# X07-X00.net
KiCad netlist of a schematic drawn in Altium Designer
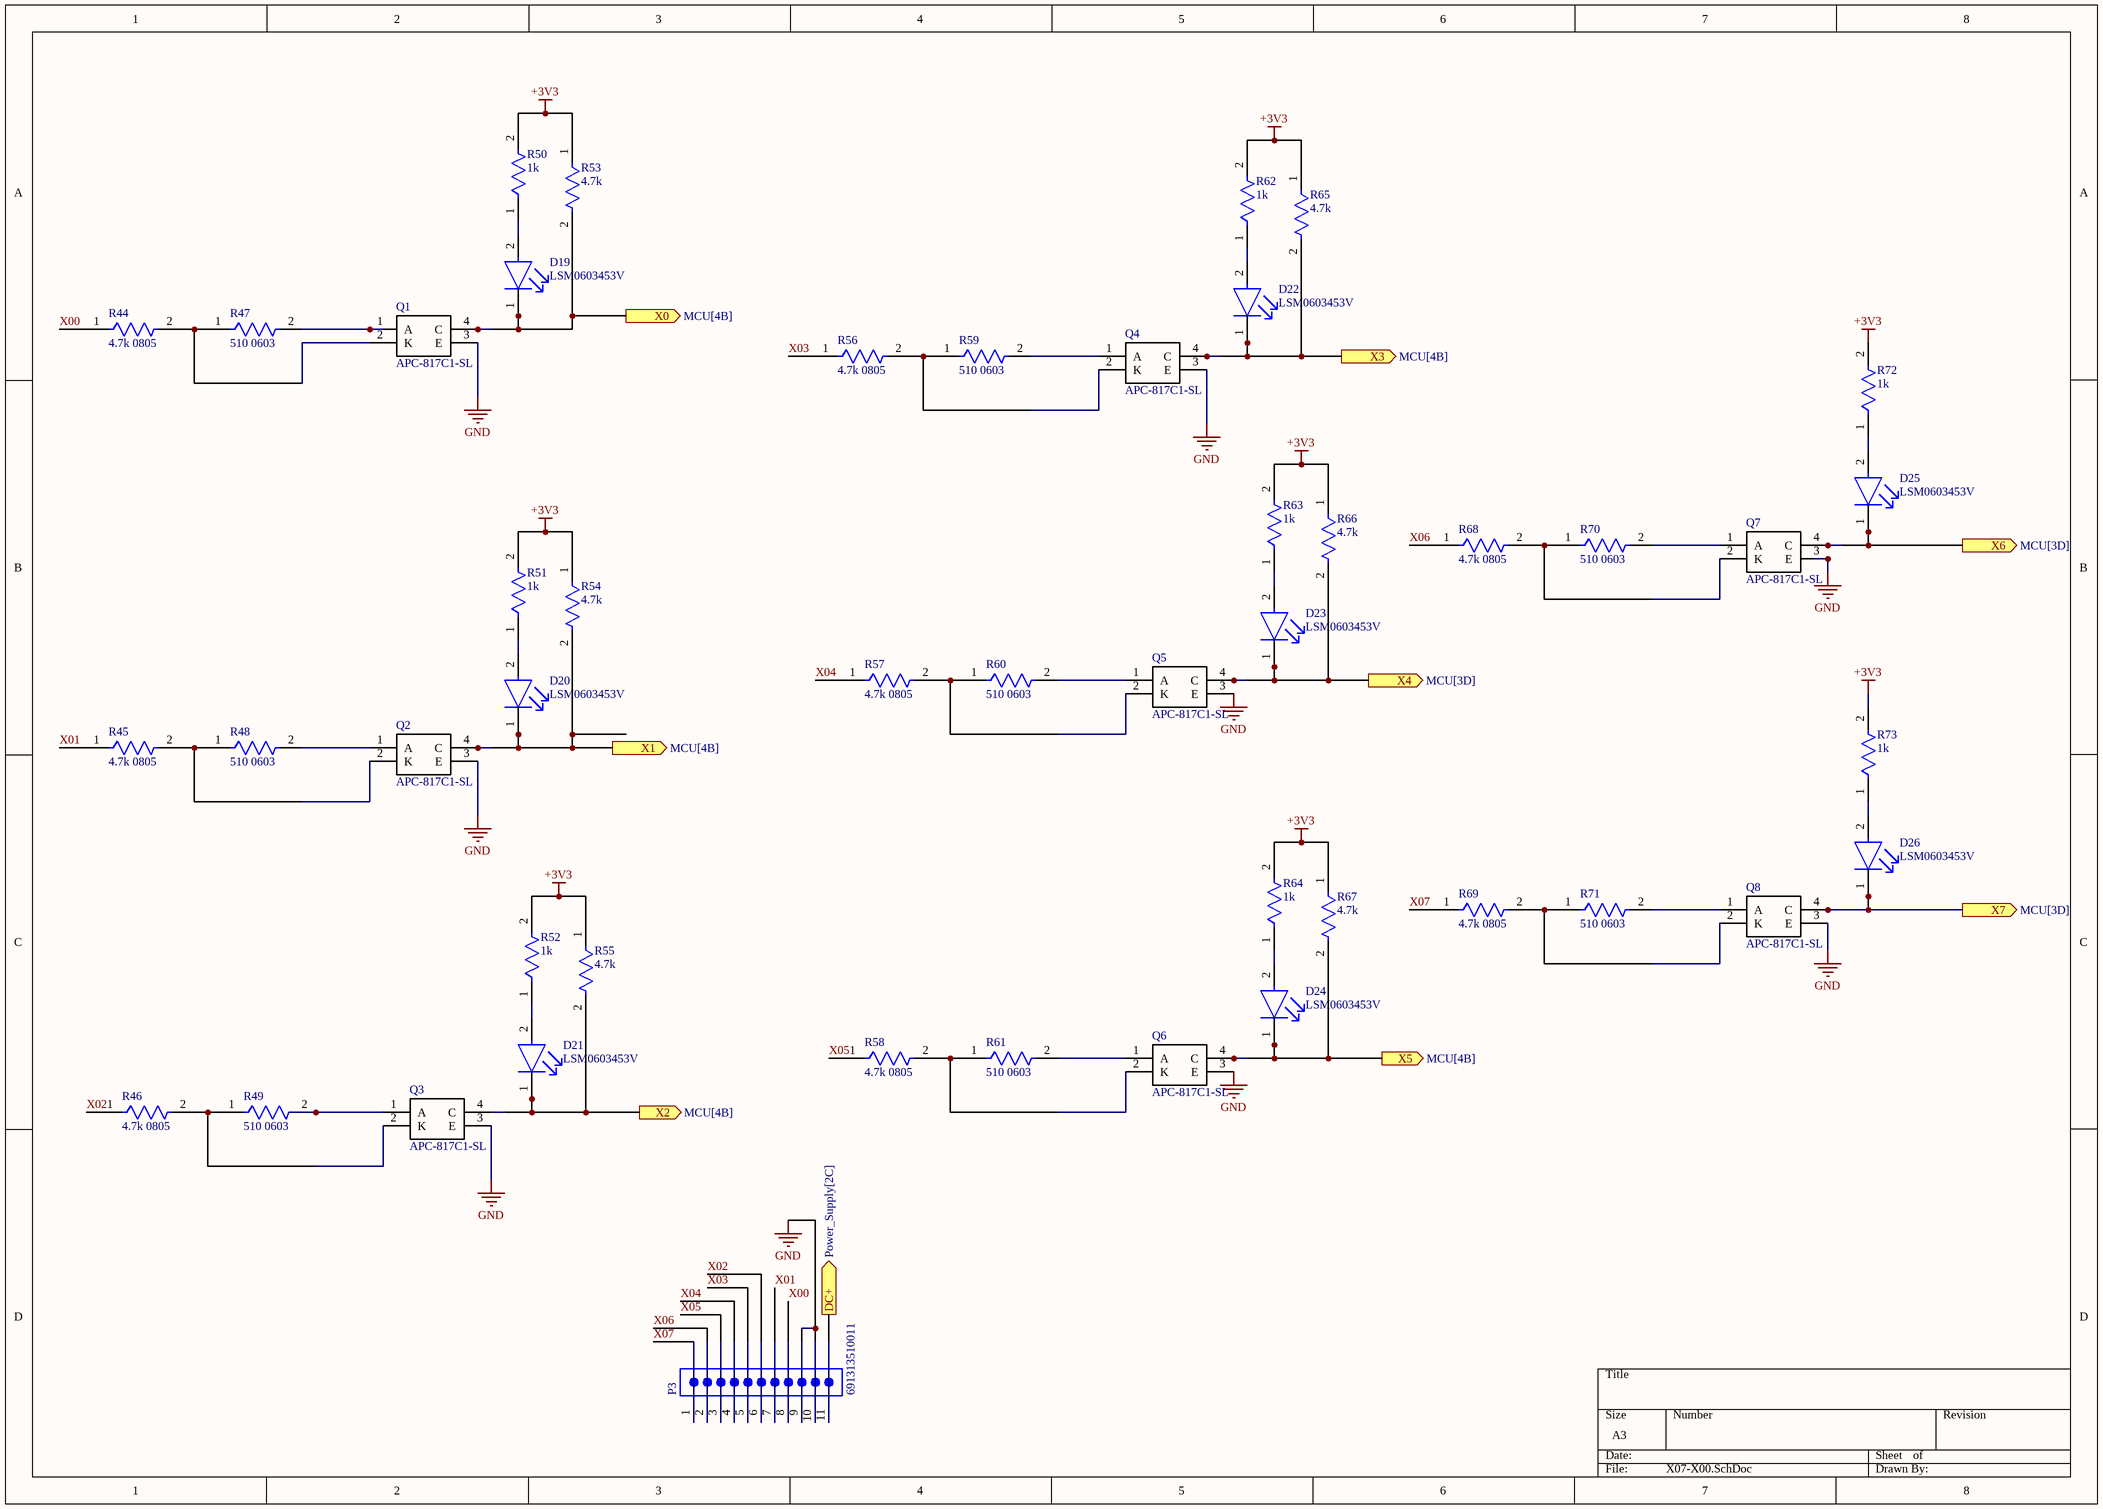
[diagram p0: X07-X00.SchDoc]

(export (version "E")
  (design (tool "Eeschema 10.0.6"))
  (components
    (comp (ref "D19")
      (value "LSM0603453V")
      (footprint "FP-LSM0603453V-MFG")
      (description "LSM0603453V LED SM 0603 3V -/1000/-mcd Green")
      (libsource (lib "Altium Content Vault") (part "8706943c75ba83719d021d2fdc84c58"))
    )
    (comp (ref "D20")
      (value "LSM0603453V")
      (footprint "FP-LSM0603453V-MFG")
      (description "LSM0603453V LED SM 0603 3V -/1000/-mcd Green")
      (libsource (lib "Altium Content Vault") (part "8706943c75ba83719d021d2fdc84c58"))
    )
    (comp (ref "D21")
      (value "LSM0603453V")
      (footprint "FP-LSM0603453V-MFG")
      (description "LSM0603453V LED SM 0603 3V -/1000/-mcd Green")
      (libsource (lib "Altium Content Vault") (part "8706943c75ba83719d021d2fdc84c58"))
    )
    (comp (ref "D22")
      (value "LSM0603453V")
      (footprint "FP-LSM0603453V-MFG")
      (description "LSM0603453V LED SM 0603 3V -/1000/-mcd Green")
      (libsource (lib "Altium Content Vault") (part "8706943c75ba83719d021d2fdc84c58"))
    )
    (comp (ref "D23")
      (value "LSM0603453V")
      (footprint "FP-LSM0603453V-MFG")
      (description "LSM0603453V LED SM 0603 3V -/1000/-mcd Green")
      (libsource (lib "Altium Content Vault") (part "8706943c75ba83719d021d2fdc84c58"))
    )
    (comp (ref "D24")
      (value "LSM0603453V")
      (footprint "FP-LSM0603453V-MFG")
      (description "LSM0603453V LED SM 0603 3V -/1000/-mcd Green")
      (libsource (lib "Altium Content Vault") (part "8706943c75ba83719d021d2fdc84c58"))
    )
    (comp (ref "D25")
      (value "LSM0603453V")
      (footprint "FP-LSM0603453V-MFG")
      (description "LSM0603453V LED SM 0603 3V -/1000/-mcd Green")
      (libsource (lib "Altium Content Vault") (part "8706943c75ba83719d021d2fdc84c58"))
    )
    (comp (ref "D26")
      (value "LSM0603453V")
      (footprint "FP-LSM0603453V-MFG")
      (description "LSM0603453V LED SM 0603 3V -/1000/-mcd Green")
      (libsource (lib "Altium Content Vault") (part "8706943c75ba83719d021d2fdc84c58"))
    )
    (comp (ref "P3")
      (value "691313510011")
      (footprint "691313510011")
      (description "Terminal Block, 5.08MM Pitch, Close Horizontal Pcb Header, 300VAC, 11 Pins")
      (libsource (lib "Altium Content Vault") (part "TBL - 1R - 11P - Male"))
    )
    (comp (ref "Q1")
      (value "APC-817C1-SL")
      (footprint "PcbLib1:APC817C1SL")
      (description "Phototransistor")
      (libsource (lib "Schlib1") (part "APC-817C1-SL"))
    )
    (comp (ref "Q2")
      (value "APC-817C1-SL")
      (footprint "PcbLib1:APC817C1SL")
      (description "Phototransistor")
      (libsource (lib "Schlib1") (part "APC-817C1-SL"))
    )
    (comp (ref "Q3")
      (value "APC-817C1-SL")
      (footprint "PcbLib1:APC817C1SL")
      (description "Phototransistor")
      (libsource (lib "Schlib1") (part "APC-817C1-SL"))
    )
    (comp (ref "Q4")
      (value "APC-817C1-SL")
      (footprint "PcbLib1:APC817C1SL")
      (description "Phototransistor")
      (libsource (lib "Schlib1") (part "APC-817C1-SL"))
    )
    (comp (ref "Q5")
      (value "APC-817C1-SL")
      (footprint "PcbLib1:APC817C1SL")
      (description "Phototransistor")
      (libsource (lib "Schlib1") (part "APC-817C1-SL"))
    )
    (comp (ref "Q6")
      (value "APC-817C1-SL")
      (footprint "PcbLib1:APC817C1SL")
      (description "Phototransistor")
      (libsource (lib "Schlib1") (part "APC-817C1-SL"))
    )
    (comp (ref "Q7")
      (value "APC-817C1-SL")
      (footprint "PcbLib1:APC817C1SL")
      (description "Phototransistor")
      (libsource (lib "Schlib1") (part "APC-817C1-SL"))
    )
    (comp (ref "Q8")
      (value "APC-817C1-SL")
      (footprint "PcbLib1:APC817C1SL")
      (description "Phototransistor")
      (libsource (lib "Schlib1") (part "APC-817C1-SL"))
    )
    (comp (ref "R44")
      (value "4.7k 0805")
      (footprint "FP-MCU0805-MFG")
      (description "RES 1.05K OHM 0.5% 1/5W 0805")
      (fields (field (name "TOLERANCE") "0.1%"))
      (libsource (lib "Altium Content Vault") (part "1029c3af85768c4190bb7ad29bc67b5"))
    )
    (comp (ref "R45")
      (value "4.7k 0805")
      (footprint "FP-MCU0805-MFG")
      (description "RES 1.05K OHM 0.5% 1/5W 0805")
      (fields (field (name "TOLERANCE") "0.1%"))
      (libsource (lib "Altium Content Vault") (part "1029c3af85768c4190bb7ad29bc67b5"))
    )
    (comp (ref "R46")
      (value "4.7k 0805")
      (footprint "FP-MCU0805-MFG")
      (description "RES 1.05K OHM 0.5% 1/5W 0805")
      (fields (field (name "TOLERANCE") "0.1%"))
      (libsource (lib "Altium Content Vault") (part "1029c3af85768c4190bb7ad29bc67b5"))
    )
    (comp (ref "R47")
      (value "510 0603")
      (footprint "FP-RMCF0603-IPC_C")
      (description "510Ω ±5% 0.1W 0603 Thick Film Chip Resistor AEC-Q200 compliant")
      (fields (field (name "TOLERANCE") "5%"))
      (libsource (lib "Altium Content Vault") (part "1029c3af85768c4190bb7ad29bc67b5"))
    )
    (comp (ref "R48")
      (value "510 0603")
      (footprint "FP-RMCF0603-IPC_C")
      (description "510Ω ±5% 0.1W 0603 Thick Film Chip Resistor AEC-Q200 compliant")
      (fields (field (name "TOLERANCE") "5%"))
      (libsource (lib "Altium Content Vault") (part "1029c3af85768c4190bb7ad29bc67b5"))
    )
    (comp (ref "R49")
      (value "510 0603")
      (footprint "FP-RMCF0603-IPC_C")
      (description "510Ω ±5% 0.1W 0603 Thick Film Chip Resistor AEC-Q200 compliant")
      (fields (field (name "TOLERANCE") "5%"))
      (libsource (lib "Altium Content Vault") (part "1029c3af85768c4190bb7ad29bc67b5"))
    )
    (comp (ref "R50")
      (value "1k")
      (footprint "FP-MCS0402-IPC_A")
      (description "RES SMD 1.2K OHM 1% 1/10W 0402")
      (libsource (lib "Altium Content Vault") (part "1029c3af85768c4190bb7ad29bc67b5"))
    )
    (comp (ref "R51")
      (value "1k")
      (footprint "FP-MCS0402-IPC_A")
      (description "RES SMD 1.2K OHM 1% 1/10W 0402")
      (libsource (lib "Altium Content Vault") (part "1029c3af85768c4190bb7ad29bc67b5"))
    )
    (comp (ref "R52")
      (value "1k")
      (footprint "FP-MCS0402-IPC_A")
      (description "RES SMD 1.2K OHM 1% 1/10W 0402")
      (libsource (lib "Altium Content Vault") (part "1029c3af85768c4190bb7ad29bc67b5"))
    )
    (comp (ref "R53")
      (value "4.7k")
      (footprint "FP-TFCR0402-IPC_A")
      (description "RES Thin Film,  4.7kΩ, 0.5%, 0.063W, 25ppm/°C, 0402")
      (libsource (lib "Altium Content Vault") (part "1029c3af85768c4190bb7ad29bc67b5"))
    )
    (comp (ref "R54")
      (value "4.7k")
      (footprint "FP-TFCR0402-IPC_A")
      (description "RES Thin Film,  4.7kΩ, 0.5%, 0.063W, 25ppm/°C, 0402")
      (libsource (lib "Altium Content Vault") (part "1029c3af85768c4190bb7ad29bc67b5"))
    )
    (comp (ref "R55")
      (value "4.7k")
      (footprint "FP-TFCR0402-IPC_A")
      (description "RES Thin Film,  4.7kΩ, 0.5%, 0.063W, 25ppm/°C, 0402")
      (libsource (lib "Altium Content Vault") (part "1029c3af85768c4190bb7ad29bc67b5"))
    )
    (comp (ref "R56")
      (value "4.7k 0805")
      (footprint "FP-MCU0805-MFG")
      (description "RES 1.05K OHM 0.5% 1/5W 0805")
      (fields (field (name "TOLERANCE") "0.1%"))
      (libsource (lib "Altium Content Vault") (part "1029c3af85768c4190bb7ad29bc67b5"))
    )
    (comp (ref "R57")
      (value "4.7k 0805")
      (footprint "FP-MCU0805-MFG")
      (description "RES 1.05K OHM 0.5% 1/5W 0805")
      (fields (field (name "TOLERANCE") "0.1%"))
      (libsource (lib "Altium Content Vault") (part "1029c3af85768c4190bb7ad29bc67b5"))
    )
    (comp (ref "R58")
      (value "4.7k 0805")
      (footprint "FP-MCU0805-MFG")
      (description "RES 1.05K OHM 0.5% 1/5W 0805")
      (fields (field (name "TOLERANCE") "0.1%"))
      (libsource (lib "Altium Content Vault") (part "1029c3af85768c4190bb7ad29bc67b5"))
    )
    (comp (ref "R59")
      (value "510 0603")
      (footprint "FP-RMCF0603-IPC_C")
      (description "510Ω ±5% 0.1W 0603 Thick Film Chip Resistor AEC-Q200 compliant")
      (fields (field (name "TOLERANCE") "5%"))
      (libsource (lib "Altium Content Vault") (part "1029c3af85768c4190bb7ad29bc67b5"))
    )
    (comp (ref "R60")
      (value "510 0603")
      (footprint "FP-RMCF0603-IPC_C")
      (description "510Ω ±5% 0.1W 0603 Thick Film Chip Resistor AEC-Q200 compliant")
      (fields (field (name "TOLERANCE") "5%"))
      (libsource (lib "Altium Content Vault") (part "1029c3af85768c4190bb7ad29bc67b5"))
    )
    (comp (ref "R61")
      (value "510 0603")
      (footprint "FP-RMCF0603-IPC_C")
      (description "510Ω ±5% 0.1W 0603 Thick Film Chip Resistor AEC-Q200 compliant")
      (fields (field (name "TOLERANCE") "5%"))
      (libsource (lib "Altium Content Vault") (part "1029c3af85768c4190bb7ad29bc67b5"))
    )
    (comp (ref "R62")
      (value "1k")
      (footprint "FP-MCS0402-IPC_A")
      (description "RES SMD 1.2K OHM 1% 1/10W 0402")
      (libsource (lib "Altium Content Vault") (part "1029c3af85768c4190bb7ad29bc67b5"))
    )
    (comp (ref "R63")
      (value "1k")
      (footprint "FP-MCS0402-IPC_A")
      (description "RES SMD 1.2K OHM 1% 1/10W 0402")
      (libsource (lib "Altium Content Vault") (part "1029c3af85768c4190bb7ad29bc67b5"))
    )
    (comp (ref "R64")
      (value "1k")
      (footprint "FP-MCS0402-IPC_A")
      (description "RES SMD 1.2K OHM 1% 1/10W 0402")
      (libsource (lib "Altium Content Vault") (part "1029c3af85768c4190bb7ad29bc67b5"))
    )
    (comp (ref "R65")
      (value "4.7k")
      (footprint "FP-TFCR0402-IPC_A")
      (description "RES Thin Film,  4.7kΩ, 0.5%, 0.063W, 25ppm/°C, 0402")
      (libsource (lib "Altium Content Vault") (part "1029c3af85768c4190bb7ad29bc67b5"))
    )
    (comp (ref "R66")
      (value "4.7k")
      (footprint "FP-TFCR0402-IPC_A")
      (description "RES Thin Film,  4.7kΩ, 0.5%, 0.063W, 25ppm/°C, 0402")
      (libsource (lib "Altium Content Vault") (part "1029c3af85768c4190bb7ad29bc67b5"))
    )
    (comp (ref "R67")
      (value "4.7k")
      (footprint "FP-TFCR0402-IPC_A")
      (description "RES Thin Film,  4.7kΩ, 0.5%, 0.063W, 25ppm/°C, 0402")
      (libsource (lib "Altium Content Vault") (part "1029c3af85768c4190bb7ad29bc67b5"))
    )
    (comp (ref "R68")
      (value "4.7k 0805")
      (footprint "FP-MCU0805-MFG")
      (description "RES 1.05K OHM 0.5% 1/5W 0805")
      (fields (field (name "TOLERANCE") "0.1%"))
      (libsource (lib "Altium Content Vault") (part "1029c3af85768c4190bb7ad29bc67b5"))
    )
    (comp (ref "R69")
      (value "4.7k 0805")
      (footprint "FP-MCU0805-MFG")
      (description "RES 1.05K OHM 0.5% 1/5W 0805")
      (fields (field (name "TOLERANCE") "0.1%"))
      (libsource (lib "Altium Content Vault") (part "1029c3af85768c4190bb7ad29bc67b5"))
    )
    (comp (ref "R70")
      (value "510 0603")
      (footprint "FP-RMCF0603-IPC_C")
      (description "510Ω ±5% 0.1W 0603 Thick Film Chip Resistor AEC-Q200 compliant")
      (fields (field (name "TOLERANCE") "5%"))
      (libsource (lib "Altium Content Vault") (part "1029c3af85768c4190bb7ad29bc67b5"))
    )
    (comp (ref "R71")
      (value "510 0603")
      (footprint "FP-RMCF0603-IPC_C")
      (description "510Ω ±5% 0.1W 0603 Thick Film Chip Resistor AEC-Q200 compliant")
      (fields (field (name "TOLERANCE") "5%"))
      (libsource (lib "Altium Content Vault") (part "1029c3af85768c4190bb7ad29bc67b5"))
    )
    (comp (ref "R72")
      (value "1k")
      (footprint "FP-MCS0402-IPC_A")
      (description "RES SMD 1.2K OHM 1% 1/10W 0402")
      (libsource (lib "Altium Content Vault") (part "1029c3af85768c4190bb7ad29bc67b5"))
    )
    (comp (ref "R73")
      (value "1k")
      (footprint "FP-MCS0402-IPC_A")
      (description "RES SMD 1.2K OHM 1% 1/10W 0402")
      (libsource (lib "Altium Content Vault") (part "1029c3af85768c4190bb7ad29bc67b5"))
    )
  )
  (nets
    (net (code "1") (name "+3V3") (class "Default")
      (node (ref "R50") (pin "2") (pinfunction "2_2") (pintype "passive"))
      (node (ref "R51") (pin "2") (pinfunction "2_2") (pintype "passive"))
      (node (ref "R52") (pin "2") (pinfunction "2_2") (pintype "passive"))
      (node (ref "R53") (pin "1") (pinfunction "1_1") (pintype "passive"))
      (node (ref "R54") (pin "1") (pinfunction "1_1") (pintype "passive"))
      (node (ref "R55") (pin "1") (pinfunction "1_1") (pintype "passive"))
      (node (ref "R62") (pin "2") (pinfunction "2_2") (pintype "passive"))
      (node (ref "R63") (pin "2") (pinfunction "2_2") (pintype "passive"))
      (node (ref "R64") (pin "2") (pinfunction "2_2") (pintype "passive"))
      (node (ref "R65") (pin "1") (pinfunction "1_1") (pintype "passive"))
      (node (ref "R66") (pin "1") (pinfunction "1_1") (pintype "passive"))
      (node (ref "R67") (pin "1") (pinfunction "1_1") (pintype "passive"))
      (node (ref "R72") (pin "2") (pinfunction "2_2") (pintype "passive"))
      (node (ref "R73") (pin "2") (pinfunction "2_2") (pintype "passive"))
    )
    (net (code "2") (name "/DC+") (class "Default")
      (node (ref "P3") (pin "11") (pinfunction "11_11") (pintype "passive"))
    )
    (net (code "3") (name "/X0") (class "Default")
      (node (ref "D19") (pin "1") (pinfunction "C_1") (pintype "passive"))
      (node (ref "Q1") (pin "4") (pinfunction "C_4") (pintype "passive"))
      (node (ref "R53") (pin "2") (pinfunction "2_2") (pintype "passive"))
    )
    (net (code "4") (name "/X00") (class "Default")
      (node (ref "P3") (pin "8") (pinfunction "8_8") (pintype "passive"))
      (node (ref "R44") (pin "1") (pinfunction "1_1") (pintype "passive"))
    )
    (net (code "5") (name "/X01") (class "Default")
      (node (ref "P3") (pin "7") (pinfunction "7_7") (pintype "passive"))
      (node (ref "R45") (pin "1") (pinfunction "1_1") (pintype "passive"))
    )
    (net (code "6") (name "/X1") (class "Default")
      (node (ref "D20") (pin "1") (pinfunction "C_1") (pintype "passive"))
      (node (ref "Q2") (pin "4") (pinfunction "C_4") (pintype "passive"))
      (node (ref "R54") (pin "2") (pinfunction "2_2") (pintype "passive"))
    )
    (net (code "7") (name "/X02") (class "Default")
      (node (ref "P3") (pin "6") (pinfunction "6_6") (pintype "passive"))
      (node (ref "R46") (pin "1") (pinfunction "1_1") (pintype "passive"))
    )
    (net (code "8") (name "/X2") (class "Default")
      (node (ref "D21") (pin "1") (pinfunction "C_1") (pintype "passive"))
      (node (ref "Q3") (pin "4") (pinfunction "C_4") (pintype "passive"))
      (node (ref "R55") (pin "2") (pinfunction "2_2") (pintype "passive"))
    )
    (net (code "9") (name "/X3") (class "Default")
      (node (ref "D22") (pin "1") (pinfunction "C_1") (pintype "passive"))
      (node (ref "Q4") (pin "4") (pinfunction "C_4") (pintype "passive"))
      (node (ref "R65") (pin "2") (pinfunction "2_2") (pintype "passive"))
    )
    (net (code "10") (name "/X03") (class "Default")
      (node (ref "P3") (pin "5") (pinfunction "5_5") (pintype "passive"))
      (node (ref "R56") (pin "1") (pinfunction "1_1") (pintype "passive"))
    )
    (net (code "11") (name "/X04") (class "Default")
      (node (ref "P3") (pin "4") (pinfunction "4_4") (pintype "passive"))
      (node (ref "R57") (pin "1") (pinfunction "1_1") (pintype "passive"))
    )
    (net (code "12") (name "/X4") (class "Default")
      (node (ref "D23") (pin "1") (pinfunction "C_1") (pintype "passive"))
      (node (ref "Q5") (pin "4") (pinfunction "C_4") (pintype "passive"))
      (node (ref "R66") (pin "2") (pinfunction "2_2") (pintype "passive"))
    )
    (net (code "13") (name "/X5") (class "Default")
      (node (ref "D24") (pin "1") (pinfunction "C_1") (pintype "passive"))
      (node (ref "Q6") (pin "4") (pinfunction "C_4") (pintype "passive"))
      (node (ref "R67") (pin "2") (pinfunction "2_2") (pintype "passive"))
    )
    (net (code "14") (name "/X05") (class "Default")
      (node (ref "P3") (pin "3") (pinfunction "3_3") (pintype "passive"))
      (node (ref "R58") (pin "1") (pinfunction "1_1") (pintype "passive"))
    )
    (net (code "15") (name "/X06") (class "Default")
      (node (ref "P3") (pin "2") (pinfunction "2_2") (pintype "passive"))
      (node (ref "R68") (pin "1") (pinfunction "1_1") (pintype "passive"))
    )
    (net (code "16") (name "/X6") (class "Default")
      (node (ref "D25") (pin "1") (pinfunction "C_1") (pintype "passive"))
      (node (ref "Q7") (pin "4") (pinfunction "C_4") (pintype "passive"))
    )
    (net (code "17") (name "/X7") (class "Default")
      (node (ref "D26") (pin "1") (pinfunction "C_1") (pintype "passive"))
      (node (ref "Q8") (pin "4") (pinfunction "C_4") (pintype "passive"))
    )
    (net (code "18") (name "/X07") (class "Default")
      (node (ref "P3") (pin "1") (pinfunction "1_1") (pintype "passive"))
      (node (ref "R69") (pin "1") (pinfunction "1_1") (pintype "passive"))
    )
    (net (code "19") (name "GND") (class "Default")
      (node (ref "P3") (pin "10") (pinfunction "10_10") (pintype "passive"))
      (node (ref "P3") (pin "9") (pinfunction "9_9") (pintype "passive"))
      (node (ref "Q1") (pin "3") (pinfunction "E_3") (pintype "passive"))
      (node (ref "Q2") (pin "3") (pinfunction "E_3") (pintype "passive"))
      (node (ref "Q3") (pin "3") (pinfunction "E_3") (pintype "passive"))
      (node (ref "Q4") (pin "3") (pinfunction "E_3") (pintype "passive"))
      (node (ref "Q5") (pin "3") (pinfunction "E_3") (pintype "passive"))
      (node (ref "Q6") (pin "3") (pinfunction "E_3") (pintype "passive"))
      (node (ref "Q7") (pin "3") (pinfunction "E_3") (pintype "passive"))
      (node (ref "Q8") (pin "3") (pinfunction "E_3") (pintype "passive"))
    )
    (net (code "20") (name "Net-(D19-A)") (class "Default")
      (node (ref "D19") (pin "2") (pinfunction "A_2") (pintype "passive"))
      (node (ref "R50") (pin "1") (pinfunction "1_1") (pintype "passive"))
    )
    (net (code "21") (name "Net-(D20-A)") (class "Default")
      (node (ref "D20") (pin "2") (pinfunction "A_2") (pintype "passive"))
      (node (ref "R51") (pin "1") (pinfunction "1_1") (pintype "passive"))
    )
    (net (code "22") (name "Net-(D21-A)") (class "Default")
      (node (ref "D21") (pin "2") (pinfunction "A_2") (pintype "passive"))
      (node (ref "R52") (pin "1") (pinfunction "1_1") (pintype "passive"))
    )
    (net (code "23") (name "Net-(D22-A)") (class "Default")
      (node (ref "D22") (pin "2") (pinfunction "A_2") (pintype "passive"))
      (node (ref "R62") (pin "1") (pinfunction "1_1") (pintype "passive"))
    )
    (net (code "24") (name "Net-(D23-A)") (class "Default")
      (node (ref "D23") (pin "2") (pinfunction "A_2") (pintype "passive"))
      (node (ref "R63") (pin "1") (pinfunction "1_1") (pintype "passive"))
    )
    (net (code "25") (name "Net-(D24-A)") (class "Default")
      (node (ref "D24") (pin "2") (pinfunction "A_2") (pintype "passive"))
      (node (ref "R64") (pin "1") (pinfunction "1_1") (pintype "passive"))
    )
    (net (code "26") (name "Net-(D25-A)") (class "Default")
      (node (ref "D25") (pin "2") (pinfunction "A_2") (pintype "passive"))
      (node (ref "R72") (pin "1") (pinfunction "1_1") (pintype "passive"))
    )
    (net (code "27") (name "Net-(D26-A)") (class "Default")
      (node (ref "D26") (pin "2") (pinfunction "A_2") (pintype "passive"))
      (node (ref "R73") (pin "1") (pinfunction "1_1") (pintype "passive"))
    )
    (net (code "28") (name "Net-(Q1-A)") (class "Default")
      (node (ref "Q1") (pin "1") (pinfunction "A_1") (pintype "passive"))
      (node (ref "R47") (pin "2") (pinfunction "2_2") (pintype "passive"))
    )
    (net (code "29") (name "Net-(Q1-K)") (class "Default")
      (node (ref "Q1") (pin "2") (pinfunction "K_2") (pintype "passive"))
      (node (ref "R44") (pin "2") (pinfunction "2_2") (pintype "passive"))
      (node (ref "R47") (pin "1") (pinfunction "1_1") (pintype "passive"))
    )
    (net (code "30") (name "Net-(Q2-A)") (class "Default")
      (node (ref "Q2") (pin "1") (pinfunction "A_1") (pintype "passive"))
      (node (ref "R48") (pin "2") (pinfunction "2_2") (pintype "passive"))
    )
    (net (code "31") (name "Net-(Q2-K)") (class "Default")
      (node (ref "Q2") (pin "2") (pinfunction "K_2") (pintype "passive"))
      (node (ref "R45") (pin "2") (pinfunction "2_2") (pintype "passive"))
      (node (ref "R48") (pin "1") (pinfunction "1_1") (pintype "passive"))
    )
    (net (code "32") (name "Net-(Q3-A)") (class "Default")
      (node (ref "Q3") (pin "1") (pinfunction "A_1") (pintype "passive"))
      (node (ref "R49") (pin "2") (pinfunction "2_2") (pintype "passive"))
    )
    (net (code "33") (name "Net-(Q3-K)") (class "Default")
      (node (ref "Q3") (pin "2") (pinfunction "K_2") (pintype "passive"))
      (node (ref "R46") (pin "2") (pinfunction "2_2") (pintype "passive"))
      (node (ref "R49") (pin "1") (pinfunction "1_1") (pintype "passive"))
    )
    (net (code "34") (name "Net-(Q4-A)") (class "Default")
      (node (ref "Q4") (pin "1") (pinfunction "A_1") (pintype "passive"))
      (node (ref "R59") (pin "2") (pinfunction "2_2") (pintype "passive"))
    )
    (net (code "35") (name "Net-(Q4-K)") (class "Default")
      (node (ref "Q4") (pin "2") (pinfunction "K_2") (pintype "passive"))
      (node (ref "R56") (pin "2") (pinfunction "2_2") (pintype "passive"))
      (node (ref "R59") (pin "1") (pinfunction "1_1") (pintype "passive"))
    )
    (net (code "36") (name "Net-(Q5-A)") (class "Default")
      (node (ref "Q5") (pin "1") (pinfunction "A_1") (pintype "passive"))
      (node (ref "R60") (pin "2") (pinfunction "2_2") (pintype "passive"))
    )
    (net (code "37") (name "Net-(Q5-K)") (class "Default")
      (node (ref "Q5") (pin "2") (pinfunction "K_2") (pintype "passive"))
      (node (ref "R57") (pin "2") (pinfunction "2_2") (pintype "passive"))
      (node (ref "R60") (pin "1") (pinfunction "1_1") (pintype "passive"))
    )
    (net (code "38") (name "Net-(Q6-A)") (class "Default")
      (node (ref "Q6") (pin "1") (pinfunction "A_1") (pintype "passive"))
      (node (ref "R61") (pin "2") (pinfunction "2_2") (pintype "passive"))
    )
    (net (code "39") (name "Net-(Q6-K)") (class "Default")
      (node (ref "Q6") (pin "2") (pinfunction "K_2") (pintype "passive"))
      (node (ref "R58") (pin "2") (pinfunction "2_2") (pintype "passive"))
      (node (ref "R61") (pin "1") (pinfunction "1_1") (pintype "passive"))
    )
    (net (code "40") (name "Net-(Q7-A)") (class "Default")
      (node (ref "Q7") (pin "1") (pinfunction "A_1") (pintype "passive"))
      (node (ref "R70") (pin "2") (pinfunction "2_2") (pintype "passive"))
    )
    (net (code "41") (name "Net-(Q7-K)") (class "Default")
      (node (ref "Q7") (pin "2") (pinfunction "K_2") (pintype "passive"))
      (node (ref "R68") (pin "2") (pinfunction "2_2") (pintype "passive"))
      (node (ref "R70") (pin "1") (pinfunction "1_1") (pintype "passive"))
    )
    (net (code "42") (name "Net-(Q8-A)") (class "Default")
      (node (ref "Q8") (pin "1") (pinfunction "A_1") (pintype "passive"))
      (node (ref "R71") (pin "2") (pinfunction "2_2") (pintype "passive"))
    )
    (net (code "43") (name "Net-(Q8-K)") (class "Default")
      (node (ref "Q8") (pin "2") (pinfunction "K_2") (pintype "passive"))
      (node (ref "R69") (pin "2") (pinfunction "2_2") (pintype "passive"))
      (node (ref "R71") (pin "1") (pinfunction "1_1") (pintype "passive"))
    )
  )
)
